# SCH.net
KiCad netlist of a schematic drawn in Altium Designer
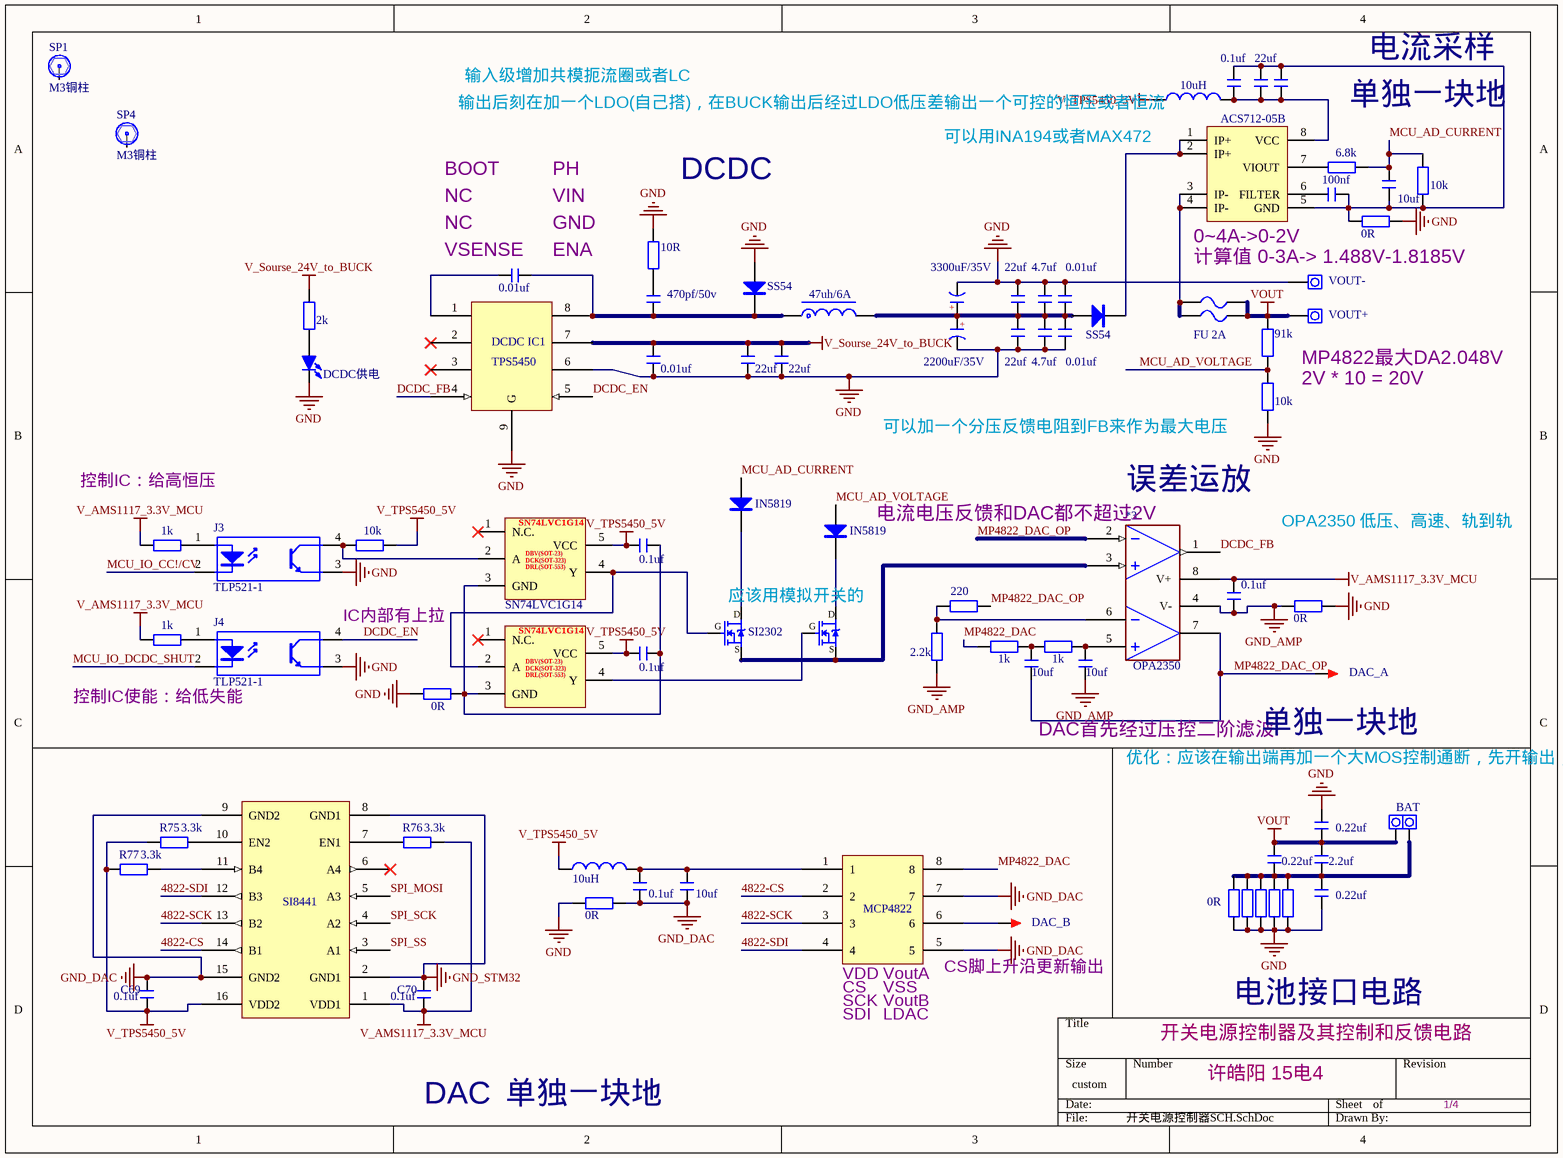
[diagram p0: 开关电源控制器SCH.SchDoc]

(export (version "E")
  (design (tool "Eeschema 10.0.6"))
  (components
    (comp (ref "*2")
      (value "SN74LVC1G14")
      (footprint "SOT23-5N")
      (libsource (lib "逻辑门器件") (part "SN74LVC1G14"))
    )
    (comp (ref "*3") (value "OPA2350") (footprint "SOP8_M") (libsource (lib "IC_temp") (part "OPA2277")))
    (comp (ref "*4")
      (value "SN74LVC1G14")
      (footprint "SOT23-5N")
      (libsource (lib "逻辑门器件") (part "SN74LVC1G14"))
    )
    (comp (ref "*5") (value "SI8441") (footprint "SOP16W_N") (libsource (lib "IC_temp") (part "SI8441")))
    (comp (ref "*6") (value "MCP4822") (footprint "SOP8_M") (libsource (lib "IC_temp") (part "8")))
    (comp (ref "7")
      (value "10R")
      (footprint "R 0805_M")
      (description "贴片电阻")
      (libsource (lib "3.1   - 电阻-电容-电感") (part "R"))
    )
    (comp (ref "8")
      (value "SS54")
      (footprint "SMA")
      (description "肖特基二极管")
      (libsource (lib "8.1   - 二极管-整流桥") (part "SS34"))
    )
    (comp (ref "9")
      (value "SS54")
      (footprint "SMA")
      (description "肖特基二极管")
      (libsource (lib "8.1   - 二极管-整流桥") (part "SS34"))
    )
    (comp (ref "10")
      (value "2k")
      (footprint "R 0805_M")
      (description "贴片电阻")
      (libsource (lib "3.1   - 电阻-电容-电感") (part "R"))
    )
    (comp (ref "11.")
      (value "91k")
      (footprint "R 0805_M")
      (description "贴片电阻")
      (libsource (lib "3.1   - 电阻-电容-电感") (part "R"))
    )
    (comp (ref "12.")
      (value "10k")
      (footprint "R 0805_M")
      (description "贴片电阻")
      (libsource (lib "3.1   - 电阻-电容-电感") (part "R"))
    )
    (comp (ref "13")
      (value "220")
      (footprint "R 0805_M")
      (description "贴片电阻")
      (libsource (lib "3.1   - 电阻-电容-电感") (part "R"))
    )
    (comp (ref "14")
      (value "0R")
      (footprint "R 0805_M")
      (description "贴片电阻")
      (libsource (lib "3.1   - 电阻-电容-电感") (part "R"))
    )
    (comp (ref "15")
      (value "1k")
      (footprint "R 0805_M")
      (description "贴片电阻")
      (libsource (lib "3.1   - 电阻-电容-电感") (part "R"))
    )
    (comp (ref "16")
      (value "1k")
      (footprint "R 0805_M")
      (description "贴片电阻")
      (libsource (lib "3.1   - 电阻-电容-电感") (part "R"))
    )
    (comp (ref "17")
      (value "2.2k")
      (footprint "R 0805_M")
      (description "贴片电阻")
      (libsource (lib "3.1   - 电阻-电容-电感") (part "R"))
    )
    (comp (ref "18")
      (value "0R")
      (footprint "R 0805_M")
      (description "贴片电阻")
      (libsource (lib "3.1   - 电阻-电容-电感") (part "R"))
    )
    (comp (ref "19")
      (value "0R")
      (footprint "R 0805_M")
      (description "贴片电阻")
      (libsource (lib "3.1   - 电阻-电容-电感") (part "R"))
    )
    (comp (ref "20")
      (value "0R")
      (footprint "R 0805_M")
      (description "贴片电阻")
      (libsource (lib "3.1   - 电阻-电容-电感") (part "R"))
    )
    (comp (ref "21")
      (value "0R")
      (footprint "R 0805_M")
      (description "贴片电阻")
      (libsource (lib "3.1   - 电阻-电容-电感") (part "R"))
    )
    (comp (ref "22")
      (value "0R")
      (footprint "R 0805_M")
      (description "贴片电阻")
      (libsource (lib "3.1   - 电阻-电容-电感") (part "R"))
    )
    (comp (ref "C41")
      (value "0.1uf")
      (footprint "C 0805_M")
      (description "无极性贴片电容")
      (libsource (lib "3.1   - 电阻-电容-电感") (part "C"))
    )
    (comp (ref "C42")
      (value "22uf")
      (footprint "C 0805_M")
      (description "无极性贴片电容")
      (libsource (lib "3.1   - 电阻-电容-电感") (part "C"))
    )
    (comp (ref "C43")
      (value "22uf")
      (footprint "C 0805_M")
      (description "无极性贴片电容")
      (libsource (lib "3.1   - 电阻-电容-电感") (part "C"))
    )
    (comp (ref "C44")
      (value "100nf")
      (footprint "C 0805_M")
      (description "无极性贴片电容")
      (libsource (lib "3.1   - 电阻-电容-电感") (part "C"))
    )
    (comp (ref "C45")
      (value "10uf")
      (footprint "C 0805_M")
      (description "无极性贴片电容")
      (libsource (lib "3.1   - 电阻-电容-电感") (part "C"))
    )
    (comp (ref "C46")
      (value "0.01uf")
      (footprint "C 0805_M")
      (description "无极性贴片电容")
      (libsource (lib "3.1   - 电阻-电容-电感") (part "C"))
    )
    (comp (ref "C47")
      (value "22uf")
      (footprint "C 0805_M")
      (description "无极性贴片电容")
      (libsource (lib "3.1   - 电阻-电容-电感") (part "C"))
    )
    (comp (ref "C48")
      (value "4.7uf")
      (footprint "C 0805_M")
      (description "无极性贴片电容")
      (libsource (lib "3.1   - 电阻-电容-电感") (part "C"))
    )
    (comp (ref "C49")
      (value "0.01uf")
      (footprint "C 0805_M")
      (description "无极性贴片电容")
      (libsource (lib "3.1   - 电阻-电容-电感") (part "C"))
    )
    (comp (ref "C50")
      (value "470pf/50v")
      (footprint "C 0805_M")
      (description "无极性贴片电容")
      (libsource (lib "3.1   - 电阻-电容-电感") (part "C"))
    )
    (comp (ref "C51")
      (value "22uf")
      (footprint "C 0805_M")
      (description "无极性贴片电容")
      (libsource (lib "3.1   - 电阻-电容-电感") (part "C"))
    )
    (comp (ref "C52")
      (value "4.7uf")
      (footprint "C 0805_M")
      (description "无极性贴片电容")
      (libsource (lib "3.1   - 电阻-电容-电感") (part "C"))
    )
    (comp (ref "C53")
      (value "0.01uf")
      (footprint "C 0805_M")
      (description "无极性贴片电容")
      (libsource (lib "3.1   - 电阻-电容-电感") (part "C"))
    )
    (comp (ref "C54")
      (value "0.01uf")
      (footprint "C 0805_M")
      (description "无极性贴片电容")
      (libsource (lib "3.1   - 电阻-电容-电感") (part "C"))
    )
    (comp (ref "C56")
      (value "22uf")
      (footprint "C 0805_M")
      (description "无极性贴片电容")
      (libsource (lib "3.1   - 电阻-电容-电感") (part "C"))
    )
    (comp (ref "C57")
      (value "22uf")
      (footprint "C 0805_M")
      (description "无极性贴片电容")
      (libsource (lib "3.1   - 电阻-电容-电感") (part "C"))
    )
    (comp (ref "C58")
      (value "0.1uf")
      (footprint "C 0805_M")
      (description "无极性贴片电容")
      (libsource (lib "3.1   - 电阻-电容-电感") (part "C"))
    )
    (comp (ref "C59")
      (value "0.1uf")
      (footprint "C 0805_M")
      (description "无极性贴片电容")
      (libsource (lib "3.1   - 电阻-电容-电感") (part "C"))
    )
    (comp (ref "C60")
      (value "0.1uf")
      (footprint "C 0805_M")
      (description "无极性贴片电容")
      (libsource (lib "3.1   - 电阻-电容-电感") (part "C"))
    )
    (comp (ref "C61")
      (value "10uf")
      (footprint "C 0805_M")
      (description "无极性贴片电容")
      (libsource (lib "3.1   - 电阻-电容-电感") (part "C"))
    )
    (comp (ref "C62")
      (value "10uf")
      (footprint "C 0805_M")
      (description "无极性贴片电容")
      (libsource (lib "3.1   - 电阻-电容-电感") (part "C"))
    )
    (comp (ref "C63")
      (value "0.22uf")
      (footprint "C 0805_M")
      (description "无极性贴片电容")
      (libsource (lib "3.1   - 电阻-电容-电感") (part "C"))
    )
    (comp (ref "C64")
      (value "0.22uf")
      (footprint "C 0805_M")
      (description "无极性贴片电容")
      (libsource (lib "3.1   - 电阻-电容-电感") (part "C"))
    )
    (comp (ref "C65")
      (value "2.2uf")
      (footprint "C 0805_M")
      (description "无极性贴片电容")
      (libsource (lib "3.1   - 电阻-电容-电感") (part "C"))
    )
    (comp (ref "C66")
      (value "0.1uf")
      (footprint "C 0805_M")
      (description "无极性贴片电容")
      (libsource (lib "3.1   - 电阻-电容-电感") (part "C"))
    )
    (comp (ref "C67")
      (value "10uf")
      (footprint "C 0805_M")
      (description "无极性贴片电容")
      (libsource (lib "3.1   - 电阻-电容-电感") (part "C"))
    )
    (comp (ref "C68")
      (value "0.22uf")
      (footprint "C 0805_M")
      (description "无极性贴片电容")
      (libsource (lib "3.1   - 电阻-电容-电感") (part "C"))
    )
    (comp (ref "C69")
      (value "0.1uf")
      (footprint "C 0805_M")
      (description "无极性贴片电容")
      (libsource (lib "3.1   - 电阻-电容-电感") (part "C"))
    )
    (comp (ref "C70")
      (value "0.1uf")
      (footprint "C 0805_M")
      (description "无极性贴片电容")
      (libsource (lib "3.1   - 电阻-电容-电感") (part "C"))
    )
    (comp (ref "D00")
      (value "IN5819")
      (footprint "SOD-123")
      (description "肖特基二极管")
      (libsource (lib "8.1   - 二极管-整流桥") (part "1N5819"))
    )
    (comp (ref "D01")
      (value "IN5819")
      (footprint "SOD-123")
      (description "肖特基二极管")
      (libsource (lib "8.1   - 二极管-整流桥") (part "1N5819"))
    )
    (comp (ref "DCDC IC1") (value "TPS5450") (footprint "ESOP8_M") (libsource (lib "IC_temp") (part "ESOP8")))
    (comp (ref "E3")
      (value "3300uF/35V")
      (footprint "DIP2-5.08mm")
      (description "直插电解电容")
      (libsource (lib "3.1   - 电阻-电容-电感") (part "C-CAP"))
    )
    (comp (ref "E5")
      (value "2200uF/35V")
      (footprint "DIP2-5.08mm")
      (description "直插电解电容")
      (libsource (lib "3.1   - 电阻-电容-电感") (part "C-CAP"))
    )
    (comp (ref "F4")
      (value "FU 2A")
      (footprint "FU 1812")
      (description "贴片保险丝")
      (libsource (lib "10.1 - 保险丝-晶振") (part "FU"))
    )
    (comp (ref "F5")
      (value "FU 2A")
      (footprint "FU 1812")
      (description "贴片保险丝")
      (libsource (lib "10.1 - 保险丝-晶振") (part "FU"))
    )
    (comp (ref "H2")
      (value "VOUT-")
      (footprint "PAD1-SMD-C")
      (description "引线焊盘")
      (libsource (lib "15.1 - 未分类器件") (part "PAD1"))
    )
    (comp (ref "H3")
      (value "VOUT+")
      (footprint "PAD1-SMD-C")
      (description "引线焊盘")
      (libsource (lib "15.1 - 未分类器件") (part "PAD1"))
    )
    (comp (ref "H4")
      (value "BAT")
      (footprint "T_head")
      (description "引线焊盘")
      (libsource (lib "15.1 - 未分类器件") (part "PAD2"))
    )
    (comp (ref "IC2")
      (value "ACS712-05B")
      (footprint "SOP8_N")
      (description "电流检测芯片")
      (libsource (lib "1.1   - IC芯片") (part "ACS712"))
    )
    (comp (ref "J3")
      (value "TLP521-1")
      (footprint "SOP4-W2.54_N")
      (description "1路开关光耦")
      (libsource (lib "11.1 - 传感元件") (part "TLP521-1"))
    )
    (comp (ref "J4")
      (value "TLP521-1")
      (footprint "SOP4-W2.54_N")
      (description "1路开关光耦")
      (libsource (lib "11.1 - 传感元件") (part "TLP521-1"))
    )
    (comp (ref "L5")
      (value "10uH")
      (footprint "L 0805_M")
      (description "小功率贴片电感")
      (libsource (lib "3.1   - 电阻-电容-电感") (part "L"))
    )
    (comp (ref "L6")
      (value "47uh/6A")
      (footprint "L-SMD-0630")
      (description "功率屏蔽电感")
      (libsource (lib "3.1   - 电阻-电容-电感") (part "L-CDRH"))
    )
    (comp (ref "L7")
      (value "10uH")
      (footprint "L 0805_M")
      (description "小功率贴片电感")
      (libsource (lib "3.1   - 电阻-电容-电感") (part "L"))
    )
    (comp (ref "LED6")
      (value "DCDC供电")
      (footprint "LED 0805G")
      (description "贴片LED")
      (libsource (lib "9.1   - LED") (part "LED-SMD"))
    )
    (comp (ref "Q7")
      (value "SI2302")
      (footprint "SOT23-3N")
      (description "N沟道 20V/3A")
      (libsource (lib "6.1   - 场效应管-可控硅") (part "SI2302"))
    )
    (comp (ref "Q8")
      (value "SI2302")
      (footprint "SOT23-3N")
      (description "N沟道 20V/3A")
      (libsource (lib "6.1   - 场效应管-可控硅") (part "SI2302"))
    )
    (comp (ref "R68")
      (value "6.8k")
      (footprint "R 0805_M")
      (description "贴片电阻")
      (libsource (lib "3.1   - 电阻-电容-电感") (part "R"))
    )
    (comp (ref "R69")
      (value "10k")
      (footprint "R 0805_M")
      (description "贴片电阻")
      (libsource (lib "3.1   - 电阻-电容-电感") (part "R"))
    )
    (comp (ref "R70")
      (value "0R")
      (footprint "R 0805_M")
      (description "贴片电阻")
      (libsource (lib "3.1   - 电阻-电容-电感") (part "R"))
    )
    (comp (ref "R71")
      (value "1k")
      (footprint "R 0805_M")
      (description "贴片电阻")
      (libsource (lib "3.1   - 电阻-电容-电感") (part "R"))
    )
    (comp (ref "R72")
      (value "10k")
      (footprint "R 0805_M")
      (description "贴片电阻")
      (libsource (lib "3.1   - 电阻-电容-电感") (part "R"))
    )
    (comp (ref "R73")
      (value "1k")
      (footprint "R 0805_M")
      (description "贴片电阻")
      (libsource (lib "3.1   - 电阻-电容-电感") (part "R"))
    )
    (comp (ref "R74")
      (value "0R")
      (footprint "R 0805_M")
      (description "贴片电阻")
      (libsource (lib "3.1   - 电阻-电容-电感") (part "R"))
    )
    (comp (ref "R75")
      (value "3.3k")
      (footprint "R 0805_M")
      (description "贴片电阻")
      (libsource (lib "3.1   - 电阻-电容-电感") (part "R"))
    )
    (comp (ref "R76")
      (value "3.3k")
      (footprint "R 0805_M")
      (description "贴片电阻")
      (libsource (lib "3.1   - 电阻-电容-电感") (part "R"))
    )
    (comp (ref "R77")
      (value "3.3k")
      (footprint "R 0805_M")
      (description "贴片电阻")
      (libsource (lib "3.1   - 电阻-电容-电感") (part "R"))
    )
    (comp (ref "R78")
      (value "0R")
      (footprint "R 0805_M")
      (description "贴片电阻")
      (libsource (lib "3.1   - 电阻-电容-电感") (part "R"))
    )
    (comp (ref "SP1")
      (value "M3铜柱")
      (footprint "M3x4+6_N")
      (description "铜柱")
      (libsource (lib "15.1 - 未分类器件") (part "铜柱加头大焊盘"))
    )
    (comp (ref "SP4")
      (value "M3铜柱")
      (footprint "M3x4+6_N")
      (description "铜柱")
      (libsource (lib "15.1 - 未分类器件") (part "铜柱加头大焊盘"))
    )
    (comp (ref "TP8")
      (value "DAC_A")
      (footprint "TEST 1")
      (description "测试点")
      (libsource (lib "15.1 - 未分类器件") (part "TEST"))
    )
    (comp (ref "TP9")
      (value "DAC_B")
      (footprint "TEST 1")
      (description "测试点")
      (libsource (lib "15.1 - 未分类器件") (part "TEST"))
    )
  )
  (nets
    (net (code "1") (name "/4822-CS") (class "Default")
      (node (ref "*5") (pin "14") (pinfunction "B1_14") (pintype "output"))
      (node (ref "*6") (pin "2") (pinfunction "2_2") (pintype "passive"))
    )
    (net (code "2") (name "/4822-SCK") (class "Default")
      (node (ref "*5") (pin "13") (pinfunction "B2_13") (pintype "output"))
      (node (ref "*6") (pin "3") (pinfunction "3_3") (pintype "passive"))
    )
    (net (code "3") (name "/4822-SDI") (class "Default")
      (node (ref "*5") (pin "12") (pinfunction "B3_12") (pintype "output"))
      (node (ref "*6") (pin "4") (pinfunction "4_4") (pintype "passive"))
    )
    (net (code "4") (name "/DCDC_EN") (class "Default")
      (node (ref "DCDC IC1") (pin "5") (pinfunction "5_5") (pintype "input"))
      (node (ref "J4") (pin "4") (pinfunction "C_4") (pintype "passive"))
    )
    (net (code "5") (name "/DCDC_FB") (class "Default")
      (node (ref "*3") (pin "1") (pinfunction "Out_A_1") (pintype "output"))
      (node (ref "DCDC IC1") (pin "4") (pinfunction "4_4") (pintype "input"))
    )
    (net (code "6") (name "/MCU_AD_CURRENT") (class "Default")
      (node (ref "C45") (pin "1") (pinfunction "1_1") (pintype "passive"))
      (node (ref "D00") (pin "1") (pinfunction "A_1") (pintype "passive"))
      (node (ref "R68") (pin "1") (pinfunction "1_1") (pintype "passive"))
      (node (ref "R69") (pin "1") (pinfunction "1_1") (pintype "passive"))
    )
    (net (code "7") (name "/MCU_AD_VOLTAGE") (class "Default")
      (node (ref "11.") (pin "2") (pinfunction "2_2") (pintype "passive"))
      (node (ref "12.") (pin "1") (pinfunction "1_1") (pintype "passive"))
      (node (ref "D01") (pin "1") (pinfunction "A_1") (pintype "passive"))
    )
    (net (code "8") (name "/MCU_IO_CC!{slash}CV") (class "Default")
      (node (ref "J3") (pin "2") (pinfunction "K_2") (pintype "passive"))
    )
    (net (code "9") (name "/MCU_IO_DCDC_SHUT") (class "Default")
      (node (ref "J4") (pin "2") (pinfunction "K_2") (pintype "passive"))
    )
    (net (code "10") (name "/MP4822_DAC") (class "Default")
      (node (ref "*6") (pin "8") (pinfunction "8_8") (pintype "passive"))
      (node (ref "15") (pin "2") (pinfunction "2_2") (pintype "passive"))
    )
    (net (code "11") (name "/MP4822_DAC_OP") (class "Default")
      (node (ref "*3") (pin "2") (pinfunction "In_A-_2") (pintype "input"))
      (node (ref "*3") (pin "7") (pinfunction "Out_B_7") (pintype "power_in"))
      (node (ref "13") (pin "2") (pinfunction "2_2") (pintype "passive"))
      (node (ref "C61") (pin "1") (pinfunction "1_1") (pintype "passive"))
      (node (ref "TP8") (pin "1") (pinfunction "1_1") (pintype "passive"))
    )
    (net (code "12") (name "/SPI_MOSI") (class "Default")
      (node (ref "*5") (pin "5") (pinfunction "A3_5") (pintype "input"))
    )
    (net (code "13") (name "/SPI_SCK") (class "Default")
      (node (ref "*5") (pin "4") (pinfunction "A2_4") (pintype "input"))
    )
    (net (code "14") (name "/SPI_SS") (class "Default")
      (node (ref "*5") (pin "3") (pinfunction "A1_3") (pintype "input"))
    )
    (net (code "15") (name "GND") (class "Default")
      (node (ref "12.") (pin "2") (pinfunction "2_2") (pintype "passive"))
      (node (ref "14") (pin "1") (pinfunction "1_1") (pintype "passive"))
      (node (ref "18") (pin "2") (pinfunction "2_2") (pintype "passive"))
      (node (ref "19") (pin "2") (pinfunction "2_2") (pintype "passive"))
      (node (ref "20") (pin "2") (pinfunction "2_2") (pintype "passive"))
      (node (ref "21") (pin "2") (pinfunction "2_2") (pintype "passive"))
      (node (ref "22") (pin "2") (pinfunction "2_2") (pintype "passive"))
      (node (ref "7") (pin "2") (pinfunction "2_2") (pintype "passive"))
      (node (ref "8") (pin "1") (pinfunction "A_1") (pintype "passive"))
      (node (ref "C47") (pin "2") (pinfunction "2_2") (pintype "passive"))
      (node (ref "C48") (pin "2") (pinfunction "2_2") (pintype "passive"))
      (node (ref "C49") (pin "2") (pinfunction "2_2") (pintype "passive"))
      (node (ref "C51") (pin "1") (pinfunction "1_1") (pintype "passive"))
      (node (ref "C52") (pin "1") (pinfunction "1_1") (pintype "passive"))
      (node (ref "C53") (pin "1") (pinfunction "1_1") (pintype "passive"))
      (node (ref "C54") (pin "1") (pinfunction "1_1") (pintype "passive"))
      (node (ref "C56") (pin "1") (pinfunction "1_1") (pintype "passive"))
      (node (ref "C57") (pin "1") (pinfunction "1_1") (pintype "passive"))
      (node (ref "C63") (pin "1") (pinfunction "1_1") (pintype "passive"))
      (node (ref "C68") (pin "2") (pinfunction "2_2") (pintype "passive"))
      (node (ref "DCDC IC1") (pin "6") (pinfunction "6_6") (pintype "power_in"))
      (node (ref "DCDC IC1") (pin "9") (pinfunction "G_9") (pintype "power_in"))
      (node (ref "E3") (pin "2") (pinfunction "K_2") (pintype "passive"))
      (node (ref "E5") (pin "2") (pinfunction "K_2") (pintype "passive"))
      (node (ref "H2") (pin "1") (pinfunction "1_1") (pintype "passive"))
      (node (ref "J3") (pin "3") (pinfunction "E_3") (pintype "passive"))
      (node (ref "J4") (pin "3") (pinfunction "E_3") (pintype "passive"))
      (node (ref "LED6") (pin "2") (pinfunction "K_2") (pintype "passive"))
      (node (ref "R70") (pin "1") (pinfunction "1_1") (pintype "passive"))
      (node (ref "R74") (pin "2") (pinfunction "2_2") (pintype "passive"))
      (node (ref "R78") (pin "2") (pinfunction "2_2") (pintype "passive"))
    )
    (net (code "16") (name "GND_AMP") (class "Default")
      (node (ref "*3") (pin "4") (pinfunction "V-_4") (pintype "power_in"))
      (node (ref "14") (pin "2") (pinfunction "2_2") (pintype "passive"))
      (node (ref "17") (pin "2") (pinfunction "2_2") (pintype "passive"))
      (node (ref "C59") (pin "1") (pinfunction "1_1") (pintype "passive"))
      (node (ref "C62") (pin "1") (pinfunction "1_1") (pintype "passive"))
    )
    (net (code "17") (name "GND_DAC") (class "Default")
      (node (ref "*5") (pin "15") (pinfunction "GND2_15") (pintype "power_in"))
      (node (ref "*5") (pin "9") (pinfunction "GND2_9") (pintype "power_in"))
      (node (ref "*6") (pin "5") (pinfunction "5_5") (pintype "passive"))
      (node (ref "*6") (pin "7") (pinfunction "7_7") (pintype "passive"))
      (node (ref "C66") (pin "1") (pinfunction "1_1") (pintype "passive"))
      (node (ref "C67") (pin "1") (pinfunction "1_1") (pintype "passive"))
      (node (ref "C69") (pin "2") (pinfunction "2_2") (pintype "passive"))
      (node (ref "R78") (pin "1") (pinfunction "1_1") (pintype "passive"))
    )
    (net (code "18") (name "GND_STM32") (class "Default")
      (node (ref "*5") (pin "2") (pinfunction "GND1_2") (pintype "power_in"))
      (node (ref "*5") (pin "8") (pinfunction "GND1_8") (pintype "power_in"))
      (node (ref "C70") (pin "2") (pinfunction "2_2") (pintype "passive"))
    )
    (net (code "19") (name "Net-(*2-A)") (class "Default")
      (node (ref "*2") (pin "2") (pinfunction "A_2") (pintype "passive"))
      (node (ref "J3") (pin "4") (pinfunction "C_4") (pintype "passive"))
      (node (ref "R72") (pin "1") (pinfunction "1_1") (pintype "passive"))
    )
    (net (code "20") (name "Net-(*2-GND)") (class "Default")
      (node (ref "*2") (pin "3") (pinfunction "GND_3") (pintype "passive"))
      (node (ref "*4") (pin "3") (pinfunction "GND_3") (pintype "passive"))
      (node (ref "C58") (pin "1") (pinfunction "1_1") (pintype "passive"))
      (node (ref "C60") (pin "1") (pinfunction "1_1") (pintype "passive"))
      (node (ref "R74") (pin "1") (pinfunction "1_1") (pintype "passive"))
    )
    (net (code "21") (name "Net-(*2-Y)") (class "Default")
      (node (ref "*2") (pin "4") (pinfunction "Y_4") (pintype "passive"))
      (node (ref "*4") (pin "2") (pinfunction "A_2") (pintype "passive"))
      (node (ref "Q7") (pin "1") (pinfunction "G_1") (pintype "passive"))
    )
    (net (code "22") (name "Net-(*3-In_A+)") (class "Default")
      (node (ref "*3") (pin "3") (pinfunction "In_A+_3") (pintype "input"))
      (node (ref "Q7") (pin "2") (pinfunction "S_2") (pintype "passive"))
      (node (ref "Q8") (pin "2") (pinfunction "S_2") (pintype "passive"))
    )
    (net (code "23") (name "Net-(*3-In_B+)") (class "Default")
      (node (ref "*3") (pin "5") (pinfunction "In_B+_5") (pintype "power_in"))
      (node (ref "16") (pin "1") (pinfunction "1_1") (pintype "passive"))
      (node (ref "C62") (pin "2") (pinfunction "2_2") (pintype "passive"))
    )
    (net (code "24") (name "Net-(*3-In_B-)") (class "Default")
      (node (ref "*3") (pin "6") (pinfunction "In_B-_6") (pintype "power_in"))
      (node (ref "13") (pin "1") (pinfunction "1_1") (pintype "passive"))
      (node (ref "17") (pin "1") (pinfunction "1_1") (pintype "passive"))
    )
    (net (code "25") (name "Net-(*4-Y)") (class "Default")
      (node (ref "*4") (pin "4") (pinfunction "Y_4") (pintype "passive"))
      (node (ref "Q8") (pin "1") (pinfunction "G_1") (pintype "passive"))
    )
    (net (code "26") (name "Net-(*5-B4)") (class "Default")
      (node (ref "*5") (pin "11") (pinfunction "B4_11") (pintype "input"))
      (node (ref "R77") (pin "1") (pinfunction "1_1") (pintype "passive"))
    )
    (net (code "27") (name "Net-(*5-EN1)") (class "Default")
      (node (ref "*5") (pin "7") (pinfunction "EN1_7") (pintype "power_in"))
      (node (ref "R76") (pin "2") (pinfunction "2_2") (pintype "passive"))
    )
    (net (code "28") (name "Net-(*5-EN2)") (class "Default")
      (node (ref "*5") (pin "10") (pinfunction "EN2_10") (pintype "power_in"))
      (node (ref "R75") (pin "1") (pinfunction "1_1") (pintype "passive"))
    )
    (net (code "29") (name "Net-(*6-Pad1)") (class "Default")
      (node (ref "*6") (pin "1") (pinfunction "1_1") (pintype "passive"))
      (node (ref "C66") (pin "2") (pinfunction "2_2") (pintype "passive"))
      (node (ref "C67") (pin "2") (pinfunction "2_2") (pintype "passive"))
      (node (ref "L7") (pin "2") (pinfunction "2_2") (pintype "passive"))
    )
    (net (code "30") (name "Net-(*6-Pad6)") (class "Default")
      (node (ref "*6") (pin "6") (pinfunction "6_6") (pintype "passive"))
      (node (ref "TP9") (pin "1") (pinfunction "1_1") (pintype "passive"))
    )
    (net (code "31") (name "Net-(7-Pad1)") (class "Default")
      (node (ref "7") (pin "1") (pinfunction "1_1") (pintype "passive"))
      (node (ref "C50") (pin "2") (pinfunction "2_2") (pintype "passive"))
    )
    (net (code "32") (name "Net-(8-K)") (class "Default")
      (node (ref "8") (pin "2") (pinfunction "K_2") (pintype "passive"))
      (node (ref "C46") (pin "2") (pinfunction "2_2") (pintype "passive"))
      (node (ref "C50") (pin "1") (pinfunction "1_1") (pintype "passive"))
      (node (ref "DCDC IC1") (pin "8") (pinfunction "8_8") (pintype "power_in"))
      (node (ref "L6") (pin "1") (pinfunction "1_1") (pintype "passive"))
    )
    (net (code "33") (name "Net-(9-A)") (class "Default")
      (node (ref "9") (pin "1") (pinfunction "A_1") (pintype "passive"))
      (node (ref "C47") (pin "1") (pinfunction "1_1") (pintype "passive"))
      (node (ref "C48") (pin "1") (pinfunction "1_1") (pintype "passive"))
      (node (ref "C49") (pin "1") (pinfunction "1_1") (pintype "passive"))
      (node (ref "C51") (pin "2") (pinfunction "2_2") (pintype "passive"))
      (node (ref "C52") (pin "2") (pinfunction "2_2") (pintype "passive"))
      (node (ref "C53") (pin "2") (pinfunction "2_2") (pintype "passive"))
      (node (ref "E3") (pin "1") (pinfunction "A_1") (pintype "passive"))
      (node (ref "E5") (pin "1") (pinfunction "A_1") (pintype "passive"))
      (node (ref "L6") (pin "2") (pinfunction "2_2") (pintype "passive"))
    )
    (net (code "34") (name "Net-(9-K)") (class "Default")
      (node (ref "9") (pin "2") (pinfunction "K_2") (pintype "passive"))
      (node (ref "IC2") (pin "1") (pinfunction "IP+_1") (pintype "passive"))
      (node (ref "IC2") (pin "2") (pinfunction "IP+_2") (pintype "passive"))
    )
    (net (code "35") (name "Net-(15-Pad1)") (class "Default")
      (node (ref "15") (pin "1") (pinfunction "1_1") (pintype "passive"))
      (node (ref "16") (pin "2") (pinfunction "2_2") (pintype "passive"))
      (node (ref "C61") (pin "2") (pinfunction "2_2") (pintype "passive"))
    )
    (net (code "36") (name "Net-(18-Pad1)") (class "Default")
      (node (ref "18") (pin "1") (pinfunction "1_1") (pintype "passive"))
      (node (ref "19") (pin "1") (pinfunction "1_1") (pintype "passive"))
      (node (ref "20") (pin "1") (pinfunction "1_1") (pintype "passive"))
      (node (ref "21") (pin "1") (pinfunction "1_1") (pintype "passive"))
      (node (ref "22") (pin "1") (pinfunction "1_1") (pintype "passive"))
      (node (ref "C64") (pin "2") (pinfunction "2_2") (pintype "passive"))
      (node (ref "C65") (pin "2") (pinfunction "2_2") (pintype "passive"))
      (node (ref "C68") (pin "1") (pinfunction "1_1") (pintype "passive"))
      (node (ref "H4") (pin "1") (pinfunction "1_1") (pintype "passive"))
    )
    (net (code "37") (name "Net-(C46-Pad1)") (class "Default")
      (node (ref "C46") (pin "1") (pinfunction "1_1") (pintype "passive"))
      (node (ref "DCDC IC1") (pin "1") (pinfunction "1_1") (pintype "power_in"))
    )
    (net (code "38") (name "Net-(D00-K)") (class "Default")
      (node (ref "D00") (pin "2") (pinfunction "K_2") (pintype "passive"))
      (node (ref "Q7") (pin "3") (pinfunction "D_3") (pintype "passive"))
    )
    (net (code "39") (name "Net-(D01-K)") (class "Default")
      (node (ref "D01") (pin "2") (pinfunction "K_2") (pintype "passive"))
      (node (ref "Q8") (pin "3") (pinfunction "D_3") (pintype "passive"))
    )
    (net (code "40") (name "Net-(F4-Pad1)") (class "Default")
      (node (ref "F4") (pin "1") (pinfunction "1_1") (pintype "passive"))
      (node (ref "F5") (pin "1") (pinfunction "1_1") (pintype "passive"))
      (node (ref "IC2") (pin "3") (pinfunction "IP-_3") (pintype "passive"))
      (node (ref "IC2") (pin "4") (pinfunction "IP-_4") (pintype "passive"))
    )
    (net (code "41") (name "Net-(IC2-FILTER)") (class "Default")
      (node (ref "C44") (pin "2") (pinfunction "2_2") (pintype "passive"))
      (node (ref "IC2") (pin "6") (pinfunction "FILTER_6") (pintype "passive"))
    )
    (net (code "42") (name "Net-(IC2-GND)") (class "Default")
      (node (ref "C41") (pin "2") (pinfunction "2_2") (pintype "passive"))
      (node (ref "C42") (pin "2") (pinfunction "2_2") (pintype "passive"))
      (node (ref "C43") (pin "2") (pinfunction "2_2") (pintype "passive"))
      (node (ref "C44") (pin "1") (pinfunction "1_1") (pintype "passive"))
      (node (ref "C45") (pin "2") (pinfunction "2_2") (pintype "passive"))
      (node (ref "IC2") (pin "5") (pinfunction "GND_5") (pintype "passive"))
      (node (ref "R69") (pin "2") (pinfunction "2_2") (pintype "passive"))
      (node (ref "R70") (pin "2") (pinfunction "2_2") (pintype "passive"))
    )
    (net (code "43") (name "Net-(IC2-VCC)") (class "Default")
      (node (ref "C41") (pin "1") (pinfunction "1_1") (pintype "passive"))
      (node (ref "C42") (pin "1") (pinfunction "1_1") (pintype "passive"))
      (node (ref "C43") (pin "1") (pinfunction "1_1") (pintype "passive"))
      (node (ref "IC2") (pin "8") (pinfunction "VCC_8") (pintype "passive"))
      (node (ref "L5") (pin "2") (pinfunction "2_2") (pintype "passive"))
    )
    (net (code "44") (name "Net-(IC2-VIOUT)") (class "Default")
      (node (ref "IC2") (pin "7") (pinfunction "VIOUT_7") (pintype "passive"))
      (node (ref "R68") (pin "2") (pinfunction "2_2") (pintype "passive"))
    )
    (net (code "45") (name "Net-(J3-A)") (class "Default")
      (node (ref "J3") (pin "1") (pinfunction "A_1") (pintype "passive"))
      (node (ref "R71") (pin "1") (pinfunction "1_1") (pintype "passive"))
    )
    (net (code "46") (name "Net-(J4-A)") (class "Default")
      (node (ref "J4") (pin "1") (pinfunction "A_1") (pintype "passive"))
      (node (ref "R73") (pin "1") (pinfunction "1_1") (pintype "passive"))
    )
    (net (code "47") (name "Net-(LED6-A)") (class "Default")
      (node (ref "10") (pin "1") (pinfunction "1_1") (pintype "passive"))
      (node (ref "LED6") (pin "1") (pinfunction "A_1") (pintype "passive"))
    )
    (net (code "48") (name "VOUT") (class "Default")
      (node (ref "11.") (pin "1") (pinfunction "1_1") (pintype "passive"))
      (node (ref "C63") (pin "2") (pinfunction "2_2") (pintype "passive"))
      (node (ref "C64") (pin "1") (pinfunction "1_1") (pintype "passive"))
      (node (ref "C65") (pin "1") (pinfunction "1_1") (pintype "passive"))
      (node (ref "F4") (pin "2") (pinfunction "2_2") (pintype "passive"))
      (node (ref "F5") (pin "2") (pinfunction "2_2") (pintype "passive"))
      (node (ref "H3") (pin "1") (pinfunction "1_1") (pintype "passive"))
      (node (ref "H4") (pin "2") (pinfunction "2_2") (pintype "passive"))
    )
    (net (code "49") (name "V_AMS1117_3.3V_MCU") (class "Default")
      (node (ref "*3") (pin "8") (pinfunction "V+_8") (pintype "power_in"))
      (node (ref "*5") (pin "1") (pinfunction "VDD1_1") (pintype "power_in"))
      (node (ref "C59") (pin "2") (pinfunction "2_2") (pintype "passive"))
      (node (ref "C70") (pin "1") (pinfunction "1_1") (pintype "passive"))
      (node (ref "R71") (pin "2") (pinfunction "2_2") (pintype "passive"))
      (node (ref "R73") (pin "2") (pinfunction "2_2") (pintype "passive"))
      (node (ref "R76") (pin "1") (pinfunction "1_1") (pintype "passive"))
    )
    (net (code "50") (name "V_Sourse_24V_to_BUCK") (class "Default")
      (node (ref "10") (pin "2") (pinfunction "2_2") (pintype "passive"))
      (node (ref "C54") (pin "2") (pinfunction "2_2") (pintype "passive"))
      (node (ref "C56") (pin "2") (pinfunction "2_2") (pintype "passive"))
      (node (ref "C57") (pin "2") (pinfunction "2_2") (pintype "passive"))
      (node (ref "DCDC IC1") (pin "7") (pinfunction "7_7") (pintype "power_in"))
    )
    (net (code "51") (name "V_TPS5450_5V") (class "Default")
      (node (ref "*2") (pin "5") (pinfunction "VCC_5") (pintype "passive"))
      (node (ref "*4") (pin "5") (pinfunction "VCC_5") (pintype "passive"))
      (node (ref "*5") (pin "16") (pinfunction "VDD2_16") (pintype "power_in"))
      (node (ref "C58") (pin "2") (pinfunction "2_2") (pintype "passive"))
      (node (ref "C60") (pin "2") (pinfunction "2_2") (pintype "passive"))
      (node (ref "C69") (pin "1") (pinfunction "1_1") (pintype "passive"))
      (node (ref "L5") (pin "1") (pinfunction "1_1") (pintype "passive"))
      (node (ref "L7") (pin "1") (pinfunction "1_1") (pintype "passive"))
      (node (ref "R72") (pin "2") (pinfunction "2_2") (pintype "passive"))
      (node (ref "R75") (pin "2") (pinfunction "2_2") (pintype "passive"))
      (node (ref "R77") (pin "2") (pinfunction "2_2") (pintype "passive"))
    )
    (net (code "52") (name "unconnected-(*2-N.C.-Pad1)") (class "Default")
      (node (ref "*2") (pin "1") (pinfunction "N.C._1") (pintype "passive+no_connect"))
    )
    (net (code "53") (name "unconnected-(*4-N.C.-Pad1)") (class "Default")
      (node (ref "*4") (pin "1") (pinfunction "N.C._1") (pintype "passive+no_connect"))
    )
    (net (code "54") (name "unconnected-(*5-A4-Pad6)") (class "Default")
      (node (ref "*5") (pin "6") (pinfunction "A4_6") (pintype "output+no_connect"))
    )
    (net (code "55") (name "unconnected-(DCDC IC1-Pad2)") (class "Default")
      (node (ref "DCDC IC1") (pin "2") (pinfunction "2_2") (pintype "power_in+no_connect"))
    )
    (net (code "56") (name "unconnected-(DCDC IC1-Pad3)") (class "Default")
      (node (ref "DCDC IC1") (pin "3") (pinfunction "3_3") (pintype "power_in+no_connect"))
    )
    (net (code "57") (name "unconnected-(SP1-Pad1)") (class "Default")
      (node (ref "SP1") (pin "1") (pinfunction "1_1") (pintype "passive"))
    )
    (net (code "58") (name "unconnected-(SP4-Pad1)") (class "Default")
      (node (ref "SP4") (pin "1") (pinfunction "1_1") (pintype "passive"))
    )
  )
)
